# STM32G4_microcontroller.net
KiCad netlist of a schematic drawn in Altium Designer
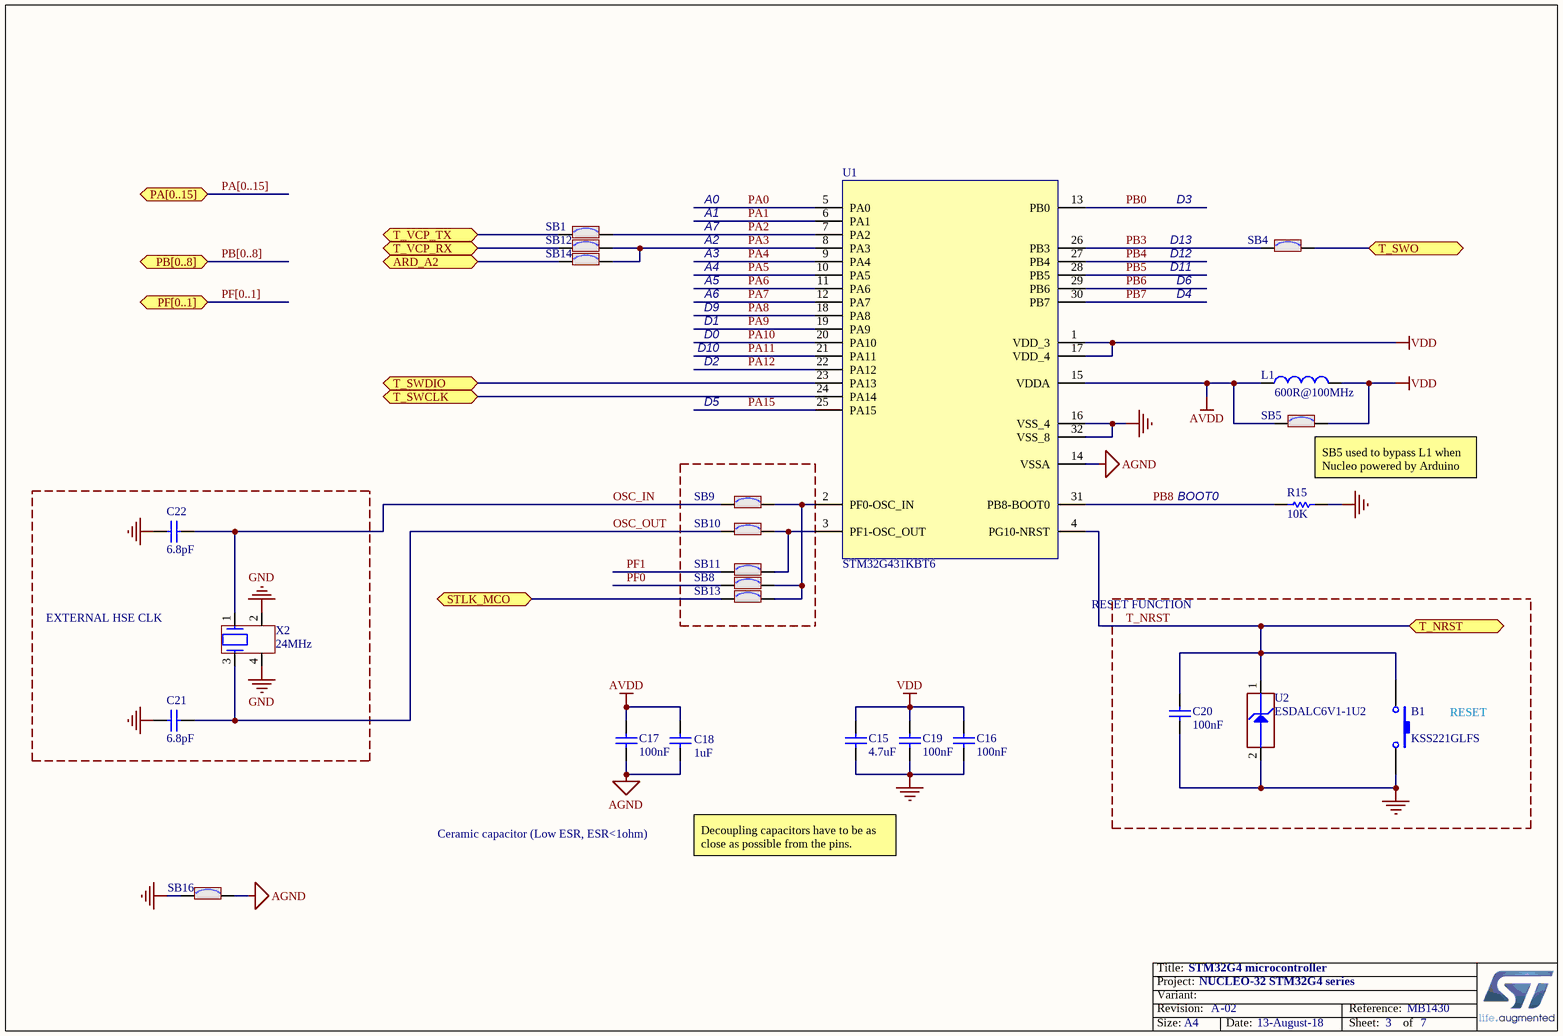
[diagram p0: STM32G4_microcontroller.SchDoc]

(export (version "E")
  (design (tool "Eeschema 10.0.6"))
  (components
    (comp (ref "B1")
      (value "KSS221GLFS")
      (footprint "SWI_C&K_ITT_KSS221G")
      (description "Subminiature Side Actuated Tact Switch for SMT - KSS series - 2.0 Newtons - Gull wing, SPST")
      (fields
        (field (name "INTERNAL_PART_NUMBER") "MCD-01335")
        (field (name "MANUFACTURER") "C&K")
        (field (name "PROVIDED_BY") "SUBCO")
      )
      (libsource (lib "MCD_PARTS_database") (part "SW-PB"))
    )
    (comp (ref "C15")
      (value "4.7uF")
      (footprint "C0603")
      (description "Capacitor, MLCC, 4.7uF, 16V, X5R, 10%, 0603, T=0.8mm")
      (fields
        (field (name "INTERNAL_PART_NUMBER") "MCD-00009")
        (field (name "MANUFACTURER_PART_NUMBER") "CC0603KRX5R7BB475")
        (field (name "PROVIDED_BY") "SUBCO")
      )
      (libsource (lib "MCD_PARTS_database") (part "Capacitor"))
    )
    (comp (ref "C16")
      (value "100nF")
      (footprint "C0402")
      (description "Capacitor, MLCC, 100nF, 16V, X7R, 10%, 0402, T=0,5mm")
      (fields
        (field (name "INTERNAL_PART_NUMBER") "MCD-00102")
        (field (name "MANUFACTURER_PART_NUMBER") "CC0402KRX7R7BB104")
        (field (name "PROVIDED_BY") "SUBCO")
      )
      (libsource (lib "MCD_PARTS_database") (part "Capacitor"))
    )
    (comp (ref "C17")
      (value "100nF")
      (footprint "C0402")
      (description "Capacitor, MLCC, 100nF, 16V, X7R, 10%, 0402, T=0,5mm")
      (fields
        (field (name "INTERNAL_PART_NUMBER") "MCD-00102")
        (field (name "MANUFACTURER_PART_NUMBER") "CC0402KRX7R7BB104")
        (field (name "PROVIDED_BY") "SUBCO")
      )
      (libsource (lib "MCD_PARTS_database") (part "Capacitor"))
    )
    (comp (ref "C18")
      (value "1uF")
      (footprint "C0603")
      (description "Capacitor, MLCC, 1uF, 16V, X5R, 10%, 0603, T=0,8mm")
      (fields
        (field (name "INTERNAL_PART_NUMBER") "MCD-00010")
        (field (name "MANUFACTURER_PART_NUMBER") "CC0603KRX5R7BB105")
        (field (name "PROVIDED_BY") "SUBCO")
      )
      (libsource (lib "MCD_PARTS_database") (part "Capacitor"))
    )
    (comp (ref "C19")
      (value "100nF")
      (footprint "C0402")
      (description "Capacitor, MLCC, 100nF, 16V, X7R, 10%, 0402, T=0,5mm")
      (fields
        (field (name "INTERNAL_PART_NUMBER") "MCD-00102")
        (field (name "MANUFACTURER_PART_NUMBER") "CC0402KRX7R7BB104")
        (field (name "PROVIDED_BY") "SUBCO")
      )
      (libsource (lib "MCD_PARTS_database") (part "Capacitor"))
    )
    (comp (ref "C20")
      (value "100nF")
      (footprint "C0402")
      (description "Capacitor, MLCC, 100nF, 16V, X7R, 10%, 0402, T=0,5mm")
      (fields
        (field (name "INTERNAL_PART_NUMBER") "MCD-00102")
        (field (name "MANUFACTURER_PART_NUMBER") "CC0402KRX7R7BB104")
        (field (name "PROVIDED_BY") "SUBCO")
      )
      (libsource (lib "MCD_PARTS_database") (part "Capacitor"))
    )
    (comp (ref "C21")
      (value "6.8pF")
      (footprint "C0402")
      (description "Capacitor, MLCC, 6.8pF, 50V, NPO, +-0.25pF, 0402, T=0.5mm")
      (fields
        (field (name "INTERNAL_PART_NUMBER") "MCD-00674")
        (field (name "MANUFACTURER_PART_NUMBER") "CC0402CRNPO9BN6R8")
        (field (name "PROVIDED_BY") "SUBCO")
      )
      (libsource (lib "MCD_PARTS_database") (part "Capacitor"))
    )
    (comp (ref "C22")
      (value "6.8pF")
      (footprint "C0402")
      (description "Capacitor, MLCC, 6.8pF, 50V, NPO, +-0.25pF, 0402, T=0.5mm")
      (fields
        (field (name "INTERNAL_PART_NUMBER") "MCD-00674")
        (field (name "MANUFACTURER_PART_NUMBER") "CC0402CRNPO9BN6R8")
        (field (name "PROVIDED_BY") "SUBCO")
      )
      (libsource (lib "MCD_PARTS_database") (part "Capacitor"))
    )
    (comp (ref "L1")
      (value "600R@100MHz")
      (footprint "L0603")
      (description "SMD Chip ferrite bead, 600R@100MHz +/-25%, 350mA, 500mohm DC, 0603, T=0.8mm")
      (fields
        (field (name "INTERNAL_PART_NUMBER") "MCD-00047")
        (field (name "MANUFACTURER_PART_NUMBER") "FCM1608KF-601T03")
        (field (name "PROVIDED_BY") "SUBCO")
      )
      (libsource (lib "MCD_PARTS_database") (part "BEAD"))
    )
    (comp (ref "R15")
      (value "10K")
      (footprint "R0603")
      (description "Resistor,10K,0603,1%,1/10W")
      (fields
        (field (name "INTERNAL_PART_NUMBER") "MCD-00220")
        (field (name "MANUFACTURER_PART_NUMBER") "RC0603FR-0710KL")
        (field (name "PROVIDED_BY") "SUBCO")
      )
      (libsource (lib "MCD_PARTS_database") (part "Resistor"))
    )
    (comp (ref "SB1")
      (value "~")
      (footprint "SOLDER-BRIDGE_R0603-0R")
      (description "Solder Bridge ON")
      (fields
        (field (name "INTERNAL_PART_NUMBER") "MCD-00071")
        (field (name "MANUFACTURER_PART_NUMBER") "RC0603JR-070RL")
        (field (name "PROVIDED_BY") "SUBCO")
      )
      (libsource (lib "MCD_PARTS_database") (part "SB_ON"))
    )
    (comp (ref "SB4")
      (value "~")
      (footprint "SOLDER-BRIDGE_R0603-0R")
      (description "Solder Bridge ON")
      (fields
        (field (name "INTERNAL_PART_NUMBER") "MCD-00071")
        (field (name "MANUFACTURER_PART_NUMBER") "RC0603JR-070RL")
        (field (name "PROVIDED_BY") "SUBCO")
      )
      (libsource (lib "MCD_PARTS_database") (part "SB_ON"))
    )
    (comp (ref "SB5")
      (value "~")
      (footprint "SOLDER-BRIDGE_R0603-0R")
      (description "Solder Bridge ON")
      (fields
        (field (name "INTERNAL_PART_NUMBER") "MCD-00071")
        (field (name "MANUFACTURER_PART_NUMBER") "RC0603JR-070RL")
        (field (name "PROVIDED_BY") "SUBCO")
      )
      (libsource (lib "MCD_PARTS_database") (part "SB_ON"))
    )
    (comp (ref "SB8")
      (value "~")
      (footprint "SOLDER-BRIDGE_R0603-0R")
      (description "Solder Bridge ON")
      (fields
        (field (name "INTERNAL_PART_NUMBER") "MCD-00071")
        (field (name "MANUFACTURER_PART_NUMBER") "RC0603JR-070RL")
        (field (name "PROVIDED_BY") "SUBCO")
      )
      (libsource (lib "MCD_PARTS_database") (part "SB_ON"))
    )
    (comp (ref "SB9")
      (value "~")
      (footprint "SOLDER-BRIDGE_R0603-0R")
      (description "Solder Bridge ON")
      (fields
        (field (name "INTERNAL_PART_NUMBER") "MCD-00071")
        (field (name "MANUFACTURER_PART_NUMBER") "RC0603JR-070RL")
        (field (name "PROVIDED_BY") "SUBCO")
      )
      (libsource (lib "MCD_PARTS_database") (part "SB_ON"))
    )
    (comp (ref "SB10")
      (value "~")
      (footprint "SOLDER-BRIDGE_R0603-0R")
      (description "Solder Bridge ON")
      (fields
        (field (name "INTERNAL_PART_NUMBER") "MCD-00071")
        (field (name "MANUFACTURER_PART_NUMBER") "RC0603JR-070RL")
        (field (name "PROVIDED_BY") "SUBCO")
      )
      (libsource (lib "MCD_PARTS_database") (part "SB_ON"))
    )
    (comp (ref "SB11")
      (value "~")
      (footprint "SOLDER-BRIDGE_R0603-0R")
      (description "Solder Bridge ON")
      (fields
        (field (name "INTERNAL_PART_NUMBER") "MCD-00071")
        (field (name "MANUFACTURER_PART_NUMBER") "RC0603JR-070RL")
        (field (name "PROVIDED_BY") "SUBCO")
      )
      (libsource (lib "MCD_PARTS_database") (part "SB_ON"))
    )
    (comp (ref "SB12")
      (value "~")
      (footprint "SOLDER-BRIDGE_R0603-0R")
      (description "Solder Bridge ON")
      (fields
        (field (name "INTERNAL_PART_NUMBER") "MCD-00071")
        (field (name "MANUFACTURER_PART_NUMBER") "RC0603JR-070RL")
        (field (name "PROVIDED_BY") "SUBCO")
      )
      (libsource (lib "MCD_PARTS_database") (part "SB_ON"))
    )
    (comp (ref "SB13")
      (value "~")
      (footprint "SOLDER-BRIDGE_R0603-0R")
      (description "Solder Bridge ON")
      (fields
        (field (name "INTERNAL_PART_NUMBER") "MCD-00071")
        (field (name "MANUFACTURER_PART_NUMBER") "RC0603JR-070RL")
        (field (name "PROVIDED_BY") "SUBCO")
      )
      (libsource (lib "MCD_PARTS_database") (part "SB_ON"))
    )
    (comp (ref "SB14")
      (value "~")
      (footprint "SOLDER-BRIDGE_R0603-0R")
      (description "Solder Bridge ON")
      (fields
        (field (name "INTERNAL_PART_NUMBER") "MCD-00071")
        (field (name "MANUFACTURER_PART_NUMBER") "RC0603JR-070RL")
        (field (name "PROVIDED_BY") "SUBCO")
      )
      (libsource (lib "MCD_PARTS_database") (part "SB_ON"))
    )
    (comp (ref "SB16")
      (value "~")
      (footprint "SOLDER-BRIDGE_R0603-0R")
      (description "Solder Bridge ON")
      (fields
        (field (name "INTERNAL_PART_NUMBER") "MCD-00071")
        (field (name "MANUFACTURER_PART_NUMBER") "RC0603JR-070RL")
        (field (name "PROVIDED_BY") "SUBCO")
      )
      (libsource (lib "MCD_PARTS_database") (part "SB_ON"))
    )
    (comp (ref "U1")
      (value "STM32G431KBT6")
      (footprint "ICC_LQFP32_7X7_P080__UFQFPN32-EPAD_5X5_P050__DI")
      (description "STM32G431, LQFP32 package, with double footprint (LQFP32_5V & UFQFPN32_A0B8)")
      (fields
        (field (name "INTERNAL_PART_NUMBER") "MCD-01396")
        (field (name "MANUFACTURER") "STMICROELECTRONICS")
        (field (name "PROVIDED_BY") "SUBCO with ST control")
      )
      (libsource (lib "MCD_PARTS_database") (part "STM32G431KBT6"))
    )
    (comp (ref "U2")
      (value "ESDALC6V1-1U2")
      (footprint "ESD_ST0201")
      (description "ESD protection 6V1")
      (fields
        (field (name "INTERNAL_PART_NUMBER") "MCD-00170")
        (field (name "MANUFACTURER") "STMICROELECTRONICS")
        (field (name "PROVIDED_BY") "SUBCO with ST control")
      )
      (libsource (lib "MCD_PARTS_database") (part "ESD-TRANSIL"))
    )
    (comp (ref "X2")
      (value "24MHz")
      (footprint "CRY_NX2016SA_4P")
      (description "24MHz crystal oscillator - Cl:6pf -")
      (fields
        (field (name "INTERNAL_PART_NUMBER") "MCD-01036")
        (field (name "MANUFACTURER_PART_NUMBER") "NX2016SA 24MHz EXS00A-CS10820")
      )
      (libsource (lib "MCD_PARTS_database") (part "XTAL_4_PINS"))
    )
  )
  (nets
    (net (code "5") (name "/ARD_A2") (class "Default")
      (node (ref "SB14") (pin "1") (pinfunction "1_1") (pintype "passive"))
    )
    (net (code "6") (name "/OSC_IN") (class "Default")
      (node (ref "C22") (pin "2") (pinfunction "2_2") (pintype "passive"))
      (node (ref "SB9") (pin "1") (pinfunction "1_1") (pintype "passive"))
      (node (ref "X2") (pin "1") (pinfunction "1_1") (pintype "passive"))
    )
    (net (code "7") (name "/OSC_OUT") (class "Default")
      (node (ref "C21") (pin "2") (pinfunction "2_2") (pintype "passive"))
      (node (ref "SB10") (pin "1") (pinfunction "1_1") (pintype "passive"))
      (node (ref "X2") (pin "3") (pinfunction "3_3") (pintype "passive"))
    )
    (net (code "8") (name "/PA0") (class "Default")
      (node (ref "U1") (pin "5") (pinfunction "PA0_5") (pintype "passive"))
    )
    (net (code "9") (name "/PA1") (class "Default")
      (node (ref "U1") (pin "6") (pinfunction "PA1_6") (pintype "passive"))
    )
    (net (code "10") (name "/PA2") (class "Default")
      (node (ref "SB1") (pin "2") (pinfunction "2_2") (pintype "passive"))
      (node (ref "U1") (pin "7") (pinfunction "PA2_7") (pintype "passive"))
    )
    (net (code "11") (name "/PA3") (class "Default")
      (node (ref "SB12") (pin "2") (pinfunction "2_2") (pintype "passive"))
      (node (ref "SB14") (pin "2") (pinfunction "2_2") (pintype "passive"))
      (node (ref "U1") (pin "8") (pinfunction "PA3_8") (pintype "passive"))
    )
    (net (code "12") (name "/PA4") (class "Default")
      (node (ref "U1") (pin "9") (pinfunction "PA4_9") (pintype "passive"))
    )
    (net (code "13") (name "/PA5") (class "Default")
      (node (ref "U1") (pin "10") (pinfunction "PA5_10") (pintype "passive"))
    )
    (net (code "14") (name "/PA6") (class "Default")
      (node (ref "U1") (pin "11") (pinfunction "PA6_11") (pintype "passive"))
    )
    (net (code "15") (name "/PA7") (class "Default")
      (node (ref "U1") (pin "12") (pinfunction "PA7_12") (pintype "passive"))
    )
    (net (code "16") (name "/PA8") (class "Default")
      (node (ref "U1") (pin "18") (pinfunction "PA8_18") (pintype "passive"))
    )
    (net (code "17") (name "/PA9") (class "Default")
      (node (ref "U1") (pin "19") (pinfunction "PA9_19") (pintype "passive"))
    )
    (net (code "18") (name "/PA10") (class "Default")
      (node (ref "U1") (pin "20") (pinfunction "PA10_20") (pintype "passive"))
    )
    (net (code "19") (name "/PA11") (class "Default")
      (node (ref "U1") (pin "21") (pinfunction "PA11_21") (pintype "passive"))
    )
    (net (code "20") (name "/PA12") (class "Default")
      (node (ref "U1") (pin "22") (pinfunction "PA12_22") (pintype "passive"))
    )
    (net (code "21") (name "/PA15") (class "Default")
      (node (ref "U1") (pin "25") (pinfunction "PA15_25") (pintype "passive"))
    )
    (net (code "23") (name "/PB0") (class "Default")
      (node (ref "U1") (pin "13") (pinfunction "PB0_13") (pintype "passive"))
    )
    (net (code "24") (name "/PB3") (class "Default")
      (node (ref "SB4") (pin "1") (pinfunction "1_1") (pintype "passive"))
      (node (ref "U1") (pin "26") (pinfunction "PB3_26") (pintype "passive"))
    )
    (net (code "25") (name "/PB4") (class "Default")
      (node (ref "U1") (pin "27") (pinfunction "PB4_27") (pintype "passive"))
    )
    (net (code "26") (name "/PB5") (class "Default")
      (node (ref "U1") (pin "28") (pinfunction "PB5_28") (pintype "passive"))
    )
    (net (code "27") (name "/PB6") (class "Default")
      (node (ref "U1") (pin "29") (pinfunction "PB6_29") (pintype "passive"))
    )
    (net (code "28") (name "/PB7") (class "Default")
      (node (ref "U1") (pin "30") (pinfunction "PB7_30") (pintype "passive"))
    )
    (net (code "29") (name "/PB8") (class "Default")
      (node (ref "R15") (pin "2") (pinfunction "2_2") (pintype "passive"))
      (node (ref "U1") (pin "31") (pinfunction "PB8-BOOT0_31") (pintype "passive"))
    )
    (net (code "31") (name "/PF0") (class "Default")
      (node (ref "SB8") (pin "1") (pinfunction "1_1") (pintype "passive"))
    )
    (net (code "32") (name "/PF1") (class "Default")
      (node (ref "SB11") (pin "1") (pinfunction "1_1") (pintype "passive"))
    )
    (net (code "34") (name "/STLK_MCO") (class "Default")
      (node (ref "SB13") (pin "1") (pinfunction "1_1") (pintype "passive"))
    )
    (net (code "35") (name "/T_NRST") (class "Default")
      (node (ref "B1") (pin "1") (pinfunction "1_1") (pintype "passive"))
      (node (ref "C20") (pin "2") (pinfunction "2_2") (pintype "passive"))
      (node (ref "U1") (pin "4") (pinfunction "PG10-NRST_4") (pintype "passive"))
      (node (ref "U2") (pin "1") (pinfunction "IO1_1") (pintype "passive"))
    )
    (net (code "36") (name "/T_SWCLK") (class "Default")
      (node (ref "U1") (pin "24") (pinfunction "PA14_24") (pintype "passive"))
    )
    (net (code "37") (name "/T_SWDIO") (class "Default")
      (node (ref "U1") (pin "23") (pinfunction "PA13_23") (pintype "passive"))
    )
    (net (code "38") (name "/T_SWO") (class "Default")
      (node (ref "SB4") (pin "2") (pinfunction "2_2") (pintype "passive"))
    )
    (net (code "39") (name "/T_VCP_RX") (class "Default")
      (node (ref "SB12") (pin "1") (pinfunction "1_1") (pintype "passive"))
    )
    (net (code "40") (name "/T_VCP_TX") (class "Default")
      (node (ref "SB1") (pin "1") (pinfunction "1_1") (pintype "passive"))
    )
    (net (code "41") (name "AGND") (class "Default")
      (node (ref "C17") (pin "1") (pinfunction "1_1") (pintype "passive"))
      (node (ref "C18") (pin "1") (pinfunction "1_1") (pintype "passive"))
      (node (ref "SB16") (pin "2") (pinfunction "2_2") (pintype "passive"))
      (node (ref "U1") (pin "14") (pinfunction "VSSA_14") (pintype "passive"))
    )
    (net (code "42") (name "AVDD") (class "Default")
      (node (ref "C17") (pin "2") (pinfunction "2_2") (pintype "passive"))
      (node (ref "C18") (pin "2") (pinfunction "2_2") (pintype "passive"))
      (node (ref "L1") (pin "1") (pinfunction "1_1") (pintype "passive"))
      (node (ref "SB5") (pin "1") (pinfunction "1_1") (pintype "passive"))
      (node (ref "U1") (pin "15") (pinfunction "VDDA_15") (pintype "passive"))
    )
    (net (code "43") (name "GND") (class "Default")
      (node (ref "B1") (pin "2") (pinfunction "2_2") (pintype "passive"))
      (node (ref "C15") (pin "1") (pinfunction "1_1") (pintype "passive"))
      (node (ref "C16") (pin "1") (pinfunction "1_1") (pintype "passive"))
      (node (ref "C19") (pin "1") (pinfunction "1_1") (pintype "passive"))
      (node (ref "C20") (pin "1") (pinfunction "1_1") (pintype "passive"))
      (node (ref "C21") (pin "1") (pinfunction "1_1") (pintype "passive"))
      (node (ref "C22") (pin "1") (pinfunction "1_1") (pintype "passive"))
      (node (ref "R15") (pin "1") (pinfunction "1_1") (pintype "passive"))
      (node (ref "SB16") (pin "1") (pinfunction "1_1") (pintype "passive"))
      (node (ref "U1") (pin "16") (pinfunction "VSS_4_16") (pintype "passive"))
      (node (ref "U1") (pin "32") (pinfunction "VSS_8_32") (pintype "passive"))
      (node (ref "U2") (pin "2") (pinfunction "GND_2") (pintype "passive"))
      (node (ref "X2") (pin "2") (pinfunction "2_2") (pintype "passive"))
      (node (ref "X2") (pin "4") (pinfunction "4_4") (pintype "passive"))
    )
    (net (code "44") (name "Net-(U1-PF0-OSC_IN)") (class "Default")
      (node (ref "SB13") (pin "2") (pinfunction "2_2") (pintype "passive"))
      (node (ref "SB8") (pin "2") (pinfunction "2_2") (pintype "passive"))
      (node (ref "SB9") (pin "2") (pinfunction "2_2") (pintype "passive"))
      (node (ref "U1") (pin "2") (pinfunction "PF0-OSC_IN_2") (pintype "passive"))
    )
    (net (code "45") (name "Net-(U1-PF1-OSC_OUT)") (class "Default")
      (node (ref "SB10") (pin "2") (pinfunction "2_2") (pintype "passive"))
      (node (ref "SB11") (pin "2") (pinfunction "2_2") (pintype "passive"))
      (node (ref "U1") (pin "3") (pinfunction "PF1-OSC_OUT_3") (pintype "passive"))
    )
    (net (code "46") (name "VDD") (class "Default")
      (node (ref "C15") (pin "2") (pinfunction "2_2") (pintype "passive"))
      (node (ref "C16") (pin "2") (pinfunction "2_2") (pintype "passive"))
      (node (ref "C19") (pin "2") (pinfunction "2_2") (pintype "passive"))
      (node (ref "L1") (pin "2") (pinfunction "2_2") (pintype "passive"))
      (node (ref "SB5") (pin "2") (pinfunction "2_2") (pintype "passive"))
      (node (ref "U1") (pin "1") (pinfunction "VDD_3_1") (pintype "passive"))
      (node (ref "U1") (pin "17") (pinfunction "VDD_4_17") (pintype "passive"))
    )
  )
)
